# rotary-encoder.net
KiCad netlist of a schematic drawn in Altium Designer
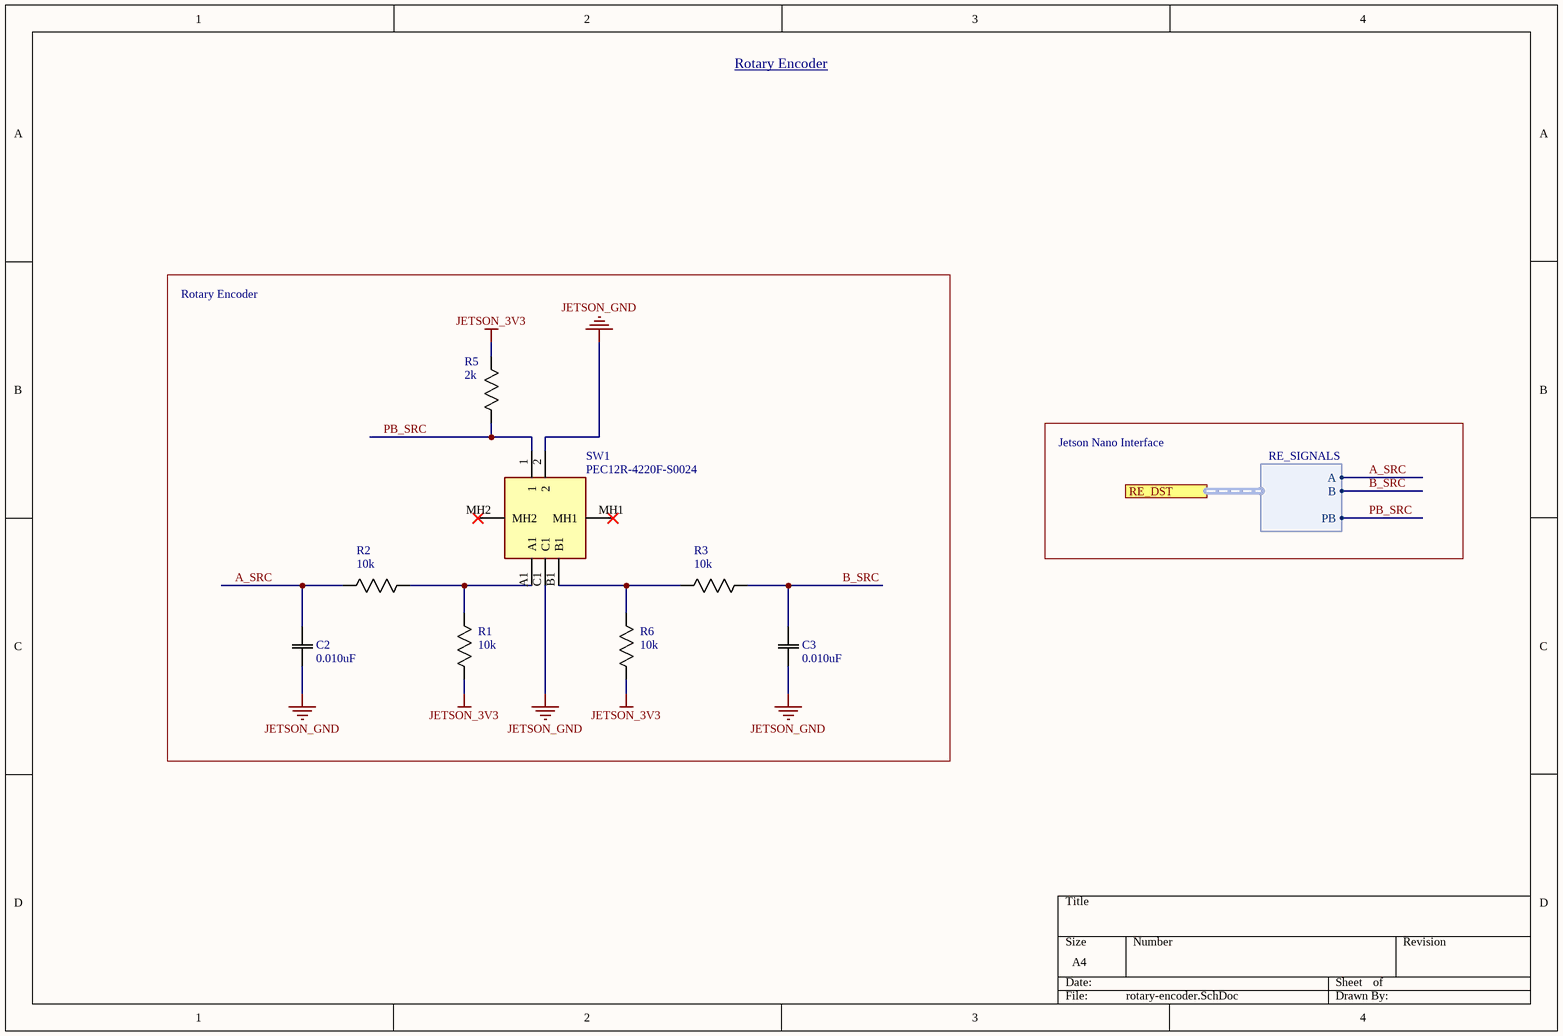
[diagram p0: rotary-encoder.SchDoc]

(export (version "E")
  (design (tool "Eeschema 10.0.6"))
  (components
    (comp (ref "C2")
      (value "0.010uF")
      (footprint "0603")
      (description "CAP CER 0.010UF 16V X5R 0603/0805")
      (fields (field (name "TOLERANCE") "10%") (field (name "PART NUMBER") "CAP 0.010uF 16V"))
      (libsource (lib "Capacitor_Library") (part "CAP 0.010uF 16V"))
    )
    (comp (ref "C3")
      (value "0.010uF")
      (footprint "0603")
      (description "CAP CER 0.010UF 16V X5R 0603/0805")
      (fields (field (name "TOLERANCE") "10%") (field (name "PART NUMBER") "CAP 0.010uF 16V"))
      (libsource (lib "Capacitor_Library") (part "CAP 0.010uF 16V"))
    )
    (comp (ref "R1")
      (value "10k")
      (footprint "0805")
      (description "RES SMD 10K OHM 1% 1/8W 0805")
      (fields (field (name "TOLERANCE") "5%") (field (name "PART NUMBER") "RES 10k 1/8W 1%"))
      (libsource (lib "") (part "RES 10k 1/8W 1%_1"))
    )
    (comp (ref "R2")
      (value "10k")
      (footprint "0805")
      (description "RES SMD 10K OHM 1% 1/8W 0805")
      (fields (field (name "TOLERANCE") "5%") (field (name "PART NUMBER") "RES 10k 1/8W 1%"))
      (libsource (lib "Resistor_Library") (part "RES 10k 1/8W 1%"))
    )
    (comp (ref "R3")
      (value "10k")
      (footprint "0805")
      (description "RES SMD 10K OHM 1% 1/8W 0805")
      (fields (field (name "TOLERANCE") "5%") (field (name "PART NUMBER") "RES 10k 1/8W 1%"))
      (libsource (lib "") (part "RES 10k 1/8W 1%_1"))
    )
    (comp (ref "R5")
      (value "2k")
      (footprint "0603")
      (description "RES SMD 2K OHM 5% 1/8W 0805")
      (fields (field (name "TOLERANCE") "5%") (field (name "PART NUMBER") "RES 2k 1/8W"))
      (libsource (lib "Resistor_Library") (part "RES 2k 1/8W"))
    )
    (comp (ref "R6")
      (value "10k")
      (footprint "0805")
      (description "RES SMD 10K OHM 1% 1/8W 0805")
      (fields (field (name "TOLERANCE") "5%") (field (name "PART NUMBER") "RES 10k 1/8W 1%"))
      (libsource (lib "Resistor_Library") (part "RES 10k 1/8W 1%"))
    )
    (comp (ref "SW1")
      (value "PEC12R-4220F-S0024")
      (footprint "PEC12R4220FS0024")
      (description "Rotary Encoder")
      (fields
        (field (name "MOUSER PART NUMBER") "652-PEC12R-4220F-S24")
        (field (name "PART NUMBER") "PEC12R4220FS0024")
      )
      (libsource (lib "Switch_Library") (part "PEC12R-4220F-S0024"))
    )
  )
  (nets
    (net (code "2") (name "/A_SRC") (class "Default")
      (node (ref "C2") (pin "2") (pinfunction "C2_2") (pintype "passive"))
      (node (ref "R2") (pin "2") (pinfunction "R2_2") (pintype "passive"))
    )
    (net (code "3") (name "/B_SRC") (class "Default")
      (node (ref "C3") (pin "2") (pinfunction "C2_2") (pintype "passive"))
      (node (ref "R3") (pin "1") (pinfunction "R1_1") (pintype "passive"))
    )
    (net (code "4") (name "/PB_SRC") (class "Default")
      (node (ref "R5") (pin "2") (pinfunction "R2_2") (pintype "passive"))
      (node (ref "SW1") (pin "1") (pinfunction "1_1") (pintype "passive"))
    )
    (net (code "6") (name "JETSON_3V3") (class "Default")
      (node (ref "R1") (pin "2") (pinfunction "R2_2") (pintype "passive"))
      (node (ref "R5") (pin "1") (pinfunction "R1_1") (pintype "passive"))
      (node (ref "R6") (pin "2") (pinfunction "R2_2") (pintype "passive"))
    )
    (net (code "7") (name "JETSON_GND") (class "Default")
      (node (ref "C2") (pin "1") (pinfunction "C1_1") (pintype "passive"))
      (node (ref "C3") (pin "1") (pinfunction "C1_1") (pintype "passive"))
      (node (ref "SW1") (pin "2") (pinfunction "2_2") (pintype "passive"))
      (node (ref "SW1") (pin "C1") (pinfunction "C1_C1") (pintype "passive"))
    )
    (net (code "8") (name "Net-(R1-R1)") (class "Default")
      (node (ref "R1") (pin "1") (pinfunction "R1_1") (pintype "passive"))
      (node (ref "R2") (pin "1") (pinfunction "R1_1") (pintype "passive"))
      (node (ref "SW1") (pin "A1") (pinfunction "A1_A1") (pintype "passive"))
    )
    (net (code "9") (name "Net-(R3-R2)") (class "Default")
      (node (ref "R3") (pin "2") (pinfunction "R2_2") (pintype "passive"))
      (node (ref "R6") (pin "1") (pinfunction "R1_1") (pintype "passive"))
      (node (ref "SW1") (pin "B1") (pinfunction "B1_B1") (pintype "passive"))
    )
    (net (code "10") (name "unconnected-(SW1-PadMH1)") (class "Default")
      (node (ref "SW1") (pin "MH1") (pinfunction "MH1_MH1") (pintype "passive+no_connect"))
    )
    (net (code "11") (name "unconnected-(SW1-PadMH2)") (class "Default")
      (node (ref "SW1") (pin "MH2") (pinfunction "MH2_MH2") (pintype "passive+no_connect"))
    )
  )
)
